# penny.net
KiCad netlist of a schematic drawn in Altium Designer
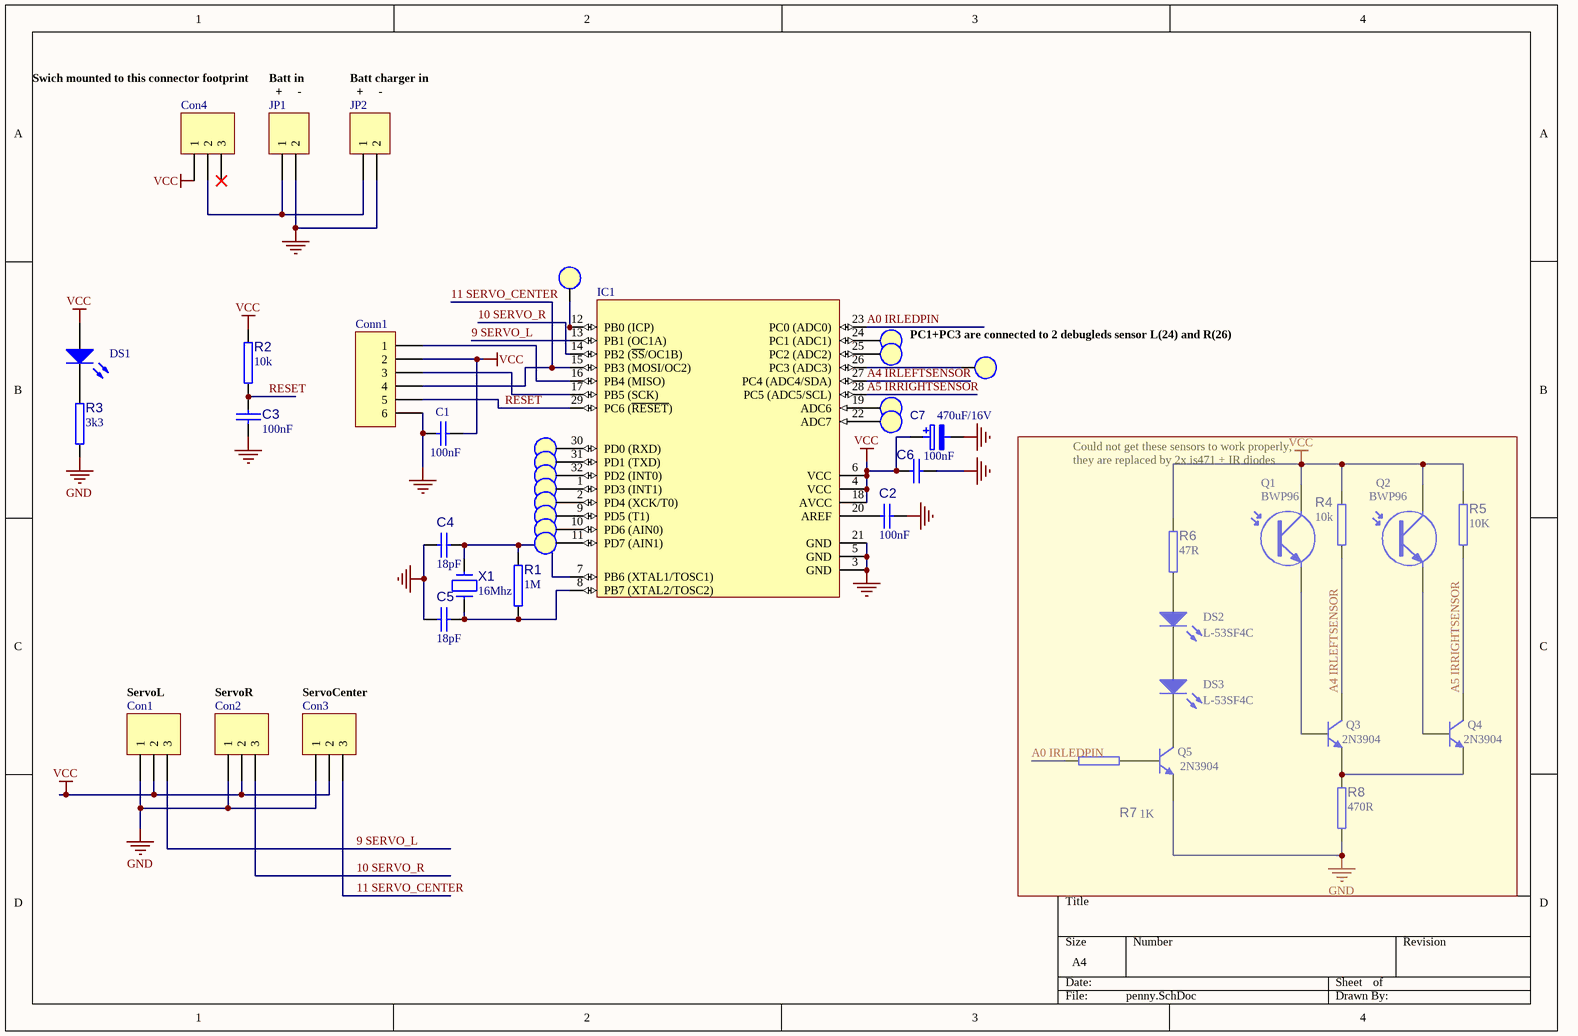
[diagram p0: penny.SchDoc]

(export (version "E")
  (design (tool "Eeschema 10.0.6"))
  (components
    (comp (ref "C1")
      (value "100nF")
      (footprint "RobotboardPCB:0805")
      (description "capacitor nonpolar")
      (libsource (lib "Robot") (part "CAP"))
    )
    (comp (ref "C2")
      (value "100nF")
      (footprint "RobotboardPCB:0805")
      (description "capacitor nonpolar")
      (libsource (lib "Robot") (part "CAP 100nF"))
    )
    (comp (ref "C3")
      (value "100nF")
      (footprint "RobotboardPCB:0805")
      (description "capacitor nonpolar")
      (libsource (lib "Robot") (part "CAP 100nF"))
    )
    (comp (ref "C4")
      (value "18pF")
      (footprint "RobotboardPCB:0805")
      (description "capacitor nonpolar")
      (libsource (lib "Robot") (part "CAP18pF"))
    )
    (comp (ref "C5")
      (value "18pF")
      (footprint "RobotboardPCB:0805")
      (description "capacitor nonpolar")
      (libsource (lib "Robot") (part "CAP18pF"))
    )
    (comp (ref "C6")
      (value "100nF")
      (footprint "RobotboardPCB:0805")
      (description "capacitor nonpolar")
      (libsource (lib "Robot") (part "CAP 100nF"))
    )
    (comp (ref "C7")
      (value "470uF/16V")
      (footprint "RB5-10.5")
      (libsource (lib "Robot") (part "Elco low ESR"))
    )
    (comp (ref "Con1")
      (value "~")
      (footprint "HDR1X3")
      (description "Header, 3-Pin")
      (fields (field (name "PUBLISHER") "Altium Limited"))
      (libsource (lib "Robot") (part "Header 3"))
    )
    (comp (ref "Con2")
      (value "~")
      (footprint "HDR1X3")
      (description "Header, 3-Pin")
      (fields (field (name "PUBLISHER") "Altium Limited"))
      (libsource (lib "Robot") (part "Header 3"))
    )
    (comp (ref "Con3")
      (value "~")
      (footprint "HDR1X3")
      (description "Header, 3-Pin")
      (fields (field (name "PUBLISHER") "Altium Limited"))
      (libsource (lib "Robot") (part "Header 3"))
    )
    (comp (ref "Con4")
      (value "~")
      (footprint "HDR1X3")
      (description "Header, 3-Pin")
      (fields (field (name "PUBLISHER") "Altium Limited"))
      (libsource (lib "Robot") (part "Header 3"))
    )
    (comp (ref "Conn1")
      (value "~")
      (footprint "HDR2X3")
      (description "Header, 6-Pin")
      (fields (field (name "PUBLISHER") "Altium Limited"))
      (libsource (lib "Robot") (part "Header 6"))
    )
    (comp (ref "DS1")
      (value "~")
      (footprint "LED-1")
      (description "Typical RED GaAs LED")
      (fields (field (name "PUBLISHER") "Altium Limited"))
      (libsource (lib "Robot") (part "LED1"))
    )
    (comp (ref "DS2")
      (value "L-53SF4C")
      (footprint "GL480IRled")
      (description "Typical INFRARED GaAs LED")
      (fields (field (name "MANUFACTURER") "Vishay"))
      (libsource (lib "Robot") (part "IR led"))
    )
    (comp (ref "DS3")
      (value "L-53SF4C")
      (footprint "GL480IRled")
      (description "Typical INFRARED GaAs LED")
      (fields (field (name "MANUFACTURER") "Vishay"))
      (libsource (lib "Robot") (part "IR led"))
    )
    (comp (ref "IC1")
      (value "~")
      (footprint "32A")
      (description "8-Bit AVR Microcontroller with 8K Bytes of In-System Programmable Flash Memory")
      (fields (field (name "PUBLISHER") "Altium Limited"))
      (libsource (lib "Robot") (part "ATmega8A-AU"))
    )
    (comp (ref "JP1")
      (value "~")
      (footprint "HDR1X2")
      (description "Header, 2-Pin")
      (fields (field (name "PUBLISHER") "Altium Limited"))
      (libsource (lib "Robot") (part "Header 2"))
    )
    (comp (ref "JP2")
      (value "~")
      (footprint "HDR1X2")
      (description "Header, 2-Pin")
      (fields (field (name "PUBLISHER") "Altium Limited"))
      (libsource (lib "Robot") (part "Header 2"))
    )
    (comp (ref "Q1")
      (value "BWP96")
      (footprint "BPW96")
      (description "NPN Phototransistor")
      (fields (field (name "PUBLISHER") "Altium Limited"))
      (libsource (lib "Robot") (part "Photo NPN"))
    )
    (comp (ref "Q2")
      (value "BWP96")
      (footprint "BPW96")
      (description "NPN Phototransistor")
      (fields (field (name "PUBLISHER") "Altium Limited"))
      (libsource (lib "Robot") (part "Photo NPN"))
    )
    (comp (ref "Q3")
      (value "2N3904")
      (footprint "BCY-W3/E4")
      (description "NPN General Purpose Amplifier")
      (fields (field (name "PUBLISHER") "Altium Limited"))
      (libsource (lib "Miscellaneous Devices") (part "2N3904"))
    )
    (comp (ref "Q4")
      (value "2N3904")
      (footprint "BCY-W3/E4")
      (description "NPN General Purpose Amplifier")
      (fields (field (name "PUBLISHER") "Altium Limited"))
      (libsource (lib "Miscellaneous Devices") (part "2N3904"))
    )
    (comp (ref "Q5")
      (value "2N3904")
      (footprint "BCY-W3/E4")
      (description "NPN General Purpose Amplifier")
      (fields (field (name "PUBLISHER") "Altium Limited"))
      (libsource (lib "Miscellaneous Devices") (part "2N3904"))
    )
    (comp (ref "R1")
      (value "1M")
      (footprint "RobotboardPCB:CR2012-0805")
      (description "Res 0805")
      (libsource (lib "Robot") (part "Res 0805"))
    )
    (comp (ref "R2")
      (value "10k")
      (footprint "RobotboardPCB:0805")
      (description "Res 0805 10k")
      (libsource (lib "Robot") (part "Res 0805 10k"))
    )
    (comp (ref "R3")
      (value "3k3")
      (footprint "RobotboardPCB:0805")
      (description "Res 0805 3k3")
      (libsource (lib "Robot") (part "Res 0805 3k3"))
    )
    (comp (ref "R4")
      (value "10k")
      (footprint "RobotboardPCB:0805")
      (description "Res 0805 10k")
      (libsource (lib "Robot") (part "Res 0805 10k"))
    )
    (comp (ref "R5")
      (value "10K")
      (footprint "RobotboardPCB:0805")
      (description "0805 resistor")
      (fields (field (name "MANUFACTURER") "Phycomp"))
      (libsource (lib "Robot") (part "RES 10K"))
    )
    (comp (ref "R6")
      (value "47R")
      (footprint "RobotboardPCB:0805")
      (description "Res 0805 47R")
      (libsource (lib "Robot") (part "Res 0805 47R"))
    )
    (comp (ref "R7")
      (value "1K")
      (footprint "RobotboardPCB:0805")
      (description "Res 0805 1k")
      (libsource (lib "Robot") (part "Res 0805 1k"))
    )
    (comp (ref "R8")
      (value "470R")
      (footprint "RobotboardPCB:0805")
      (description "Res 0805 470R")
      (libsource (lib "Robot") (part "Res 0805 47R"))
    )
    (comp (ref "TP1")
      (value "~")
      (footprint "experimentpad")
      (description "experimentpin")
      (fields (field (name "PUBLISHER") "GTa"))
      (libsource (lib "Robot") (part "TESTPOINT_1"))
    )
    (comp (ref "TP2")
      (value "~")
      (footprint "experimentpad")
      (description "experimentpin")
      (fields (field (name "PUBLISHER") "GTa"))
      (libsource (lib "Robot") (part "TESTPOINT_1"))
    )
    (comp (ref "TP3")
      (value "~")
      (footprint "experimentpad")
      (description "experimentpin")
      (fields (field (name "PUBLISHER") "GTa"))
      (libsource (lib "Robot") (part "TESTPOINT_1"))
    )
    (comp (ref "TP4")
      (value "~")
      (footprint "experimentpad")
      (description "experimentpin")
      (fields (field (name "PUBLISHER") "GTa"))
      (libsource (lib "Robot") (part "TESTPOINT_1"))
    )
    (comp (ref "TP5")
      (value "~")
      (footprint "experimentpad")
      (description "experimentpin")
      (fields (field (name "PUBLISHER") "GTa"))
      (libsource (lib "Robot") (part "TESTPOINT_1"))
    )
    (comp (ref "TP6")
      (value "~")
      (footprint "experimentpad")
      (description "experimentpin")
      (fields (field (name "PUBLISHER") "GTa"))
      (libsource (lib "Robot") (part "TESTPOINT_1"))
    )
    (comp (ref "TP7")
      (value "~")
      (footprint "experimentpad")
      (description "experimentpin")
      (fields (field (name "PUBLISHER") "GTa"))
      (libsource (lib "Robot") (part "TESTPOINT_1"))
    )
    (comp (ref "TP8")
      (value "~")
      (footprint "experimentpad")
      (description "experimentpin")
      (fields (field (name "PUBLISHER") "GTa"))
      (libsource (lib "Robot") (part "TESTPOINT_1"))
    )
    (comp (ref "TP9")
      (value "~")
      (footprint "experimentpad")
      (description "experimentpin")
      (fields (field (name "PUBLISHER") "GTa"))
      (libsource (lib "Robot") (part "TESTPOINT_1"))
    )
    (comp (ref "TP10")
      (value "~")
      (footprint "experimentpad")
      (description "experimentpin")
      (fields (field (name "PUBLISHER") "GTa"))
      (libsource (lib "Robot") (part "TESTPOINT_1"))
    )
    (comp (ref "TP11")
      (value "~")
      (footprint "experimentpad")
      (description "experimentpin")
      (fields (field (name "PUBLISHER") "GTa"))
      (libsource (lib "Robot") (part "TESTPOINT_1"))
    )
    (comp (ref "TP12")
      (value "~")
      (footprint "experimentpad")
      (description "experimentpin")
      (fields (field (name "PUBLISHER") "GTa"))
      (libsource (lib "Robot") (part "TESTPOINT_1"))
    )
    (comp (ref "TP13")
      (value "~")
      (footprint "experimentpad")
      (description "experimentpin")
      (fields (field (name "PUBLISHER") "GTa"))
      (libsource (lib "Robot") (part "TESTPOINT_1"))
    )
    (comp (ref "TP14")
      (value "~")
      (footprint "experimentpad")
      (description "experimentpin")
      (fields (field (name "PUBLISHER") "GTa"))
      (libsource (lib "Robot") (part "TESTPOINT_1"))
    )
    (comp (ref "X1")
      (value "16Mhz")
      (footprint "RobotboardPCB:HC49/U")
      (description "Crystal 8Mhz")
      (libsource (lib "Robot") (part "CRYSTAL 8Mhz"))
    )
  )
  (nets
    (net (code "1") (name "/9 SERVO_L") (class "Default")
      (node (ref "Con1") (pin "3") (pinfunction "3_3") (pintype "passive"))
      (node (ref "IC1") (pin "13") (pinfunction "PB1_(OC1A)_13") (pintype "bidirectional"))
    )
    (net (code "2") (name "/10 SERVO_R") (class "Default")
      (node (ref "Con2") (pin "3") (pinfunction "3_3") (pintype "passive"))
      (node (ref "IC1") (pin "14") (pinfunction "PB2_(~{SS}/OC1B)_14") (pintype "bidirectional"))
    )
    (net (code "3") (name "/11 SERVO_CENTER") (class "Default")
      (node (ref "Con3") (pin "3") (pinfunction "3_3") (pintype "passive"))
      (node (ref "Conn1") (pin "4") (pinfunction "4_4") (pintype "passive"))
      (node (ref "IC1") (pin "15") (pinfunction "PB3_(MOSI/OC2)_15") (pintype "bidirectional"))
    )
    (net (code "4") (name "/A0 IRLEDPIN") (class "Default")
      (node (ref "IC1") (pin "23") (pinfunction "PC0_(ADC0)_23") (pintype "bidirectional"))
      (node (ref "R7") (pin "1") (pintype "passive"))
    )
    (net (code "5") (name "/A4 IRLEFTSENSOR") (class "Default")
      (node (ref "IC1") (pin "27") (pinfunction "PC4_(ADC4/SDA)_27") (pintype "bidirectional"))
      (node (ref "Q3") (pin "3") (pinfunction "C_3") (pintype "passive"))
      (node (ref "R4") (pin "1") (pintype "passive"))
    )
    (net (code "6") (name "/A5 IRRIGHTSENSOR") (class "Default")
      (node (ref "IC1") (pin "28") (pinfunction "PC5_(ADC5/SCL)_28") (pintype "bidirectional"))
      (node (ref "Q4") (pin "3") (pinfunction "C_3") (pintype "passive"))
      (node (ref "R5") (pin "1") (pintype "passive"))
    )
    (net (code "7") (name "/RESET") (class "Default")
      (node (ref "C3") (pin "1") (pintype "passive"))
      (node (ref "Conn1") (pin "5") (pinfunction "5_5") (pintype "passive"))
      (node (ref "IC1") (pin "29") (pinfunction "PC6_(~{RESET})_29") (pintype "bidirectional"))
      (node (ref "R2") (pin "1") (pintype "passive"))
    )
    (net (code "8") (name "GND") (class "Default")
      (node (ref "C1") (pin "1") (pintype "passive"))
      (node (ref "C2") (pin "2") (pintype "passive"))
      (node (ref "C3") (pin "2") (pintype "passive"))
      (node (ref "C4") (pin "1") (pintype "passive"))
      (node (ref "C5") (pin "1") (pintype "passive"))
      (node (ref "C6") (pin "2") (pintype "passive"))
      (node (ref "C7") (pin "2") (pintype "passive"))
      (node (ref "Con1") (pin "1") (pinfunction "1_1") (pintype "passive"))
      (node (ref "Con2") (pin "1") (pinfunction "1_1") (pintype "passive"))
      (node (ref "Con3") (pin "1") (pinfunction "1_1") (pintype "passive"))
      (node (ref "Conn1") (pin "6") (pinfunction "6_6") (pintype "passive"))
      (node (ref "IC1") (pin "21") (pinfunction "GND_21") (pintype "power_in"))
      (node (ref "IC1") (pin "3") (pinfunction "GND_3") (pintype "power_in"))
      (node (ref "IC1") (pin "5") (pinfunction "GND_5") (pintype "power_in"))
      (node (ref "JP1") (pin "2") (pinfunction "2_2") (pintype "passive"))
      (node (ref "JP2") (pin "2") (pinfunction "2_2") (pintype "passive"))
      (node (ref "Q5") (pin "1") (pinfunction "E_1") (pintype "passive"))
      (node (ref "R3") (pin "1") (pintype "passive"))
      (node (ref "R8") (pin "1") (pintype "passive"))
    )
    (net (code "9") (name "Net-(Con4-Pad2)") (class "Default")
      (node (ref "Con4") (pin "2") (pinfunction "2_2") (pintype "passive"))
      (node (ref "JP1") (pin "1") (pinfunction "1_1") (pintype "passive"))
      (node (ref "JP2") (pin "1") (pinfunction "1_1") (pintype "passive"))
    )
    (net (code "10") (name "Net-(DS1-K)") (class "Default")
      (node (ref "DS1") (pin "2") (pinfunction "K_2") (pintype "passive"))
      (node (ref "R3") (pin "2") (pintype "passive"))
    )
    (net (code "11") (name "Net-(DS2-A)") (class "Default")
      (node (ref "DS2") (pin "2") (pinfunction "A_2") (pintype "passive"))
      (node (ref "R6") (pin "1") (pintype "passive"))
    )
    (net (code "12") (name "Net-(DS2-K)") (class "Default")
      (node (ref "DS2") (pin "1") (pinfunction "K_1") (pintype "passive"))
      (node (ref "DS3") (pin "2") (pinfunction "A_2") (pintype "passive"))
    )
    (net (code "13") (name "Net-(DS3-K)") (class "Default")
      (node (ref "DS3") (pin "1") (pinfunction "K_1") (pintype "passive"))
      (node (ref "Q5") (pin "3") (pinfunction "C_3") (pintype "passive"))
    )
    (net (code "14") (name "Net-(IC1-ADC6)") (class "Default")
      (node (ref "IC1") (pin "19") (pinfunction "ADC6_19") (pintype "input"))
      (node (ref "TP6") (pin "1") (pinfunction "1_1") (pintype "passive"))
    )
    (net (code "15") (name "Net-(IC1-ADC7)") (class "Default")
      (node (ref "IC1") (pin "22") (pinfunction "ADC7_22") (pintype "input"))
      (node (ref "TP7") (pin "1") (pinfunction "1_1") (pintype "passive"))
    )
    (net (code "16") (name "Net-(IC1-AREF)") (class "Default")
      (node (ref "C2") (pin "1") (pintype "passive"))
      (node (ref "IC1") (pin "20") (pinfunction "AREF_20") (pintype "passive"))
    )
    (net (code "17") (name "Net-(IC1-PB0_(ICP))") (class "Default")
      (node (ref "IC1") (pin "12") (pinfunction "PB0_(ICP)_12") (pintype "bidirectional"))
      (node (ref "TP2") (pin "1") (pinfunction "1_1") (pintype "passive"))
    )
    (net (code "18") (name "Net-(IC1-PB4_(MISO))") (class "Default")
      (node (ref "Conn1") (pin "1") (pinfunction "1_1") (pintype "passive"))
      (node (ref "IC1") (pin "16") (pinfunction "PB4_(MISO)_16") (pintype "bidirectional"))
    )
    (net (code "19") (name "Net-(IC1-PB5_(SCK))") (class "Default")
      (node (ref "Conn1") (pin "3") (pinfunction "3_3") (pintype "passive"))
      (node (ref "IC1") (pin "17") (pinfunction "PB5_(SCK)_17") (pintype "bidirectional"))
    )
    (net (code "20") (name "Net-(IC1-PB6_(XTAL1{slash}TOSC1))") (class "Default")
      (node (ref "C4") (pin "2") (pintype "passive"))
      (node (ref "IC1") (pin "7") (pinfunction "PB6_(XTAL1/TOSC1)_7") (pintype "bidirectional"))
      (node (ref "R1") (pin "2") (pintype "passive"))
      (node (ref "X1") (pin "2") (pintype "passive"))
    )
    (net (code "21") (name "Net-(IC1-PB7_(XTAL2{slash}TOSC2))") (class "Default")
      (node (ref "C5") (pin "2") (pintype "passive"))
      (node (ref "IC1") (pin "8") (pinfunction "PB7_(XTAL2/TOSC2)_8") (pintype "bidirectional"))
      (node (ref "R1") (pin "1") (pintype "passive"))
      (node (ref "X1") (pin "1") (pintype "passive"))
    )
    (net (code "22") (name "Net-(IC1-PC1_(ADC1))") (class "Default")
      (node (ref "IC1") (pin "24") (pinfunction "PC1_(ADC1)_24") (pintype "bidirectional"))
      (node (ref "TP3") (pin "1") (pinfunction "1_1") (pintype "passive"))
    )
    (net (code "23") (name "Net-(IC1-PC2_(ADC2))") (class "Default")
      (node (ref "IC1") (pin "25") (pinfunction "PC2_(ADC2)_25") (pintype "bidirectional"))
      (node (ref "TP4") (pin "1") (pinfunction "1_1") (pintype "passive"))
    )
    (net (code "24") (name "Net-(IC1-PC3_(ADC3))") (class "Default")
      (node (ref "IC1") (pin "26") (pinfunction "PC3_(ADC3)_26") (pintype "bidirectional"))
      (node (ref "TP5") (pin "1") (pinfunction "1_1") (pintype "passive"))
    )
    (net (code "25") (name "Net-(IC1-PD0_(RXD))") (class "Default")
      (node (ref "IC1") (pin "30") (pinfunction "PD0_(RXD)_30") (pintype "bidirectional"))
      (node (ref "TP1") (pin "1") (pinfunction "1_1") (pintype "passive"))
    )
    (net (code "26") (name "Net-(IC1-PD1_(TXD))") (class "Default")
      (node (ref "IC1") (pin "31") (pinfunction "PD1_(TXD)_31") (pintype "bidirectional"))
      (node (ref "TP8") (pin "1") (pinfunction "1_1") (pintype "passive"))
    )
    (net (code "27") (name "Net-(IC1-PD2_(INT0))") (class "Default")
      (node (ref "IC1") (pin "32") (pinfunction "PD2_(INT0)_32") (pintype "bidirectional"))
      (node (ref "TP9") (pin "1") (pinfunction "1_1") (pintype "passive"))
    )
    (net (code "28") (name "Net-(IC1-PD3_(INT1))") (class "Default")
      (node (ref "IC1") (pin "1") (pinfunction "PD3_(INT1)_1") (pintype "bidirectional"))
      (node (ref "TP10") (pin "1") (pinfunction "1_1") (pintype "passive"))
    )
    (net (code "29") (name "Net-(IC1-PD4_(XCK{slash}T0))") (class "Default")
      (node (ref "IC1") (pin "2") (pinfunction "PD4_(XCK/T0)_2") (pintype "bidirectional"))
      (node (ref "TP11") (pin "1") (pinfunction "1_1") (pintype "passive"))
    )
    (net (code "30") (name "Net-(IC1-PD5_(T1))") (class "Default")
      (node (ref "IC1") (pin "9") (pinfunction "PD5_(T1)_9") (pintype "bidirectional"))
      (node (ref "TP12") (pin "1") (pinfunction "1_1") (pintype "passive"))
    )
    (net (code "31") (name "Net-(IC1-PD6_(AIN0))") (class "Default")
      (node (ref "IC1") (pin "10") (pinfunction "PD6_(AIN0)_10") (pintype "bidirectional"))
      (node (ref "TP13") (pin "1") (pinfunction "1_1") (pintype "passive"))
    )
    (net (code "32") (name "Net-(IC1-PD7_(AIN1))") (class "Default")
      (node (ref "IC1") (pin "11") (pinfunction "PD7_(AIN1)_11") (pintype "bidirectional"))
      (node (ref "TP14") (pin "1") (pinfunction "1_1") (pintype "passive"))
    )
    (net (code "33") (name "Net-(Q1-E)") (class "Default")
      (node (ref "Q1") (pin "3") (pinfunction "E_3") (pintype "passive"))
      (node (ref "Q3") (pin "2") (pinfunction "B_2") (pintype "passive"))
    )
    (net (code "34") (name "Net-(Q2-E)") (class "Default")
      (node (ref "Q2") (pin "3") (pinfunction "E_3") (pintype "passive"))
      (node (ref "Q4") (pin "2") (pinfunction "B_2") (pintype "passive"))
    )
    (net (code "35") (name "Net-(Q3-E)") (class "Default")
      (node (ref "Q3") (pin "1") (pinfunction "E_1") (pintype "passive"))
      (node (ref "Q4") (pin "1") (pinfunction "E_1") (pintype "passive"))
      (node (ref "R8") (pin "2") (pintype "passive"))
    )
    (net (code "36") (name "Net-(Q5-B)") (class "Default")
      (node (ref "Q5") (pin "2") (pinfunction "B_2") (pintype "passive"))
      (node (ref "R7") (pin "2") (pintype "passive"))
    )
    (net (code "37") (name "VCC") (class "Default")
      (node (ref "C1") (pin "2") (pintype "passive"))
      (node (ref "C6") (pin "1") (pintype "passive"))
      (node (ref "C7") (pin "1") (pintype "passive"))
      (node (ref "Con1") (pin "2") (pinfunction "2_2") (pintype "passive"))
      (node (ref "Con2") (pin "2") (pinfunction "2_2") (pintype "passive"))
      (node (ref "Con3") (pin "2") (pinfunction "2_2") (pintype "passive"))
      (node (ref "Con4") (pin "1") (pinfunction "1_1") (pintype "passive"))
      (node (ref "Conn1") (pin "2") (pinfunction "2_2") (pintype "passive"))
      (node (ref "DS1") (pin "1") (pinfunction "A_1") (pintype "passive"))
      (node (ref "IC1") (pin "18") (pinfunction "AVCC_18") (pintype "power_in"))
      (node (ref "IC1") (pin "4") (pinfunction "VCC_4") (pintype "power_in"))
      (node (ref "IC1") (pin "6") (pinfunction "VCC_6") (pintype "power_in"))
      (node (ref "Q1") (pin "1") (pinfunction "C_1") (pintype "passive"))
      (node (ref "Q2") (pin "1") (pinfunction "C_1") (pintype "passive"))
      (node (ref "R2") (pin "2") (pintype "passive"))
      (node (ref "R4") (pin "2") (pintype "passive"))
      (node (ref "R5") (pin "2") (pintype "passive"))
      (node (ref "R6") (pin "2") (pintype "passive"))
    )
    (net (code "38") (name "unconnected-(Con4-Pad3)") (class "Default")
      (node (ref "Con4") (pin "3") (pinfunction "3_3") (pintype "passive+no_connect"))
    )
  )
)
